# MCU.net
KiCad netlist of a schematic drawn in Altium Designer
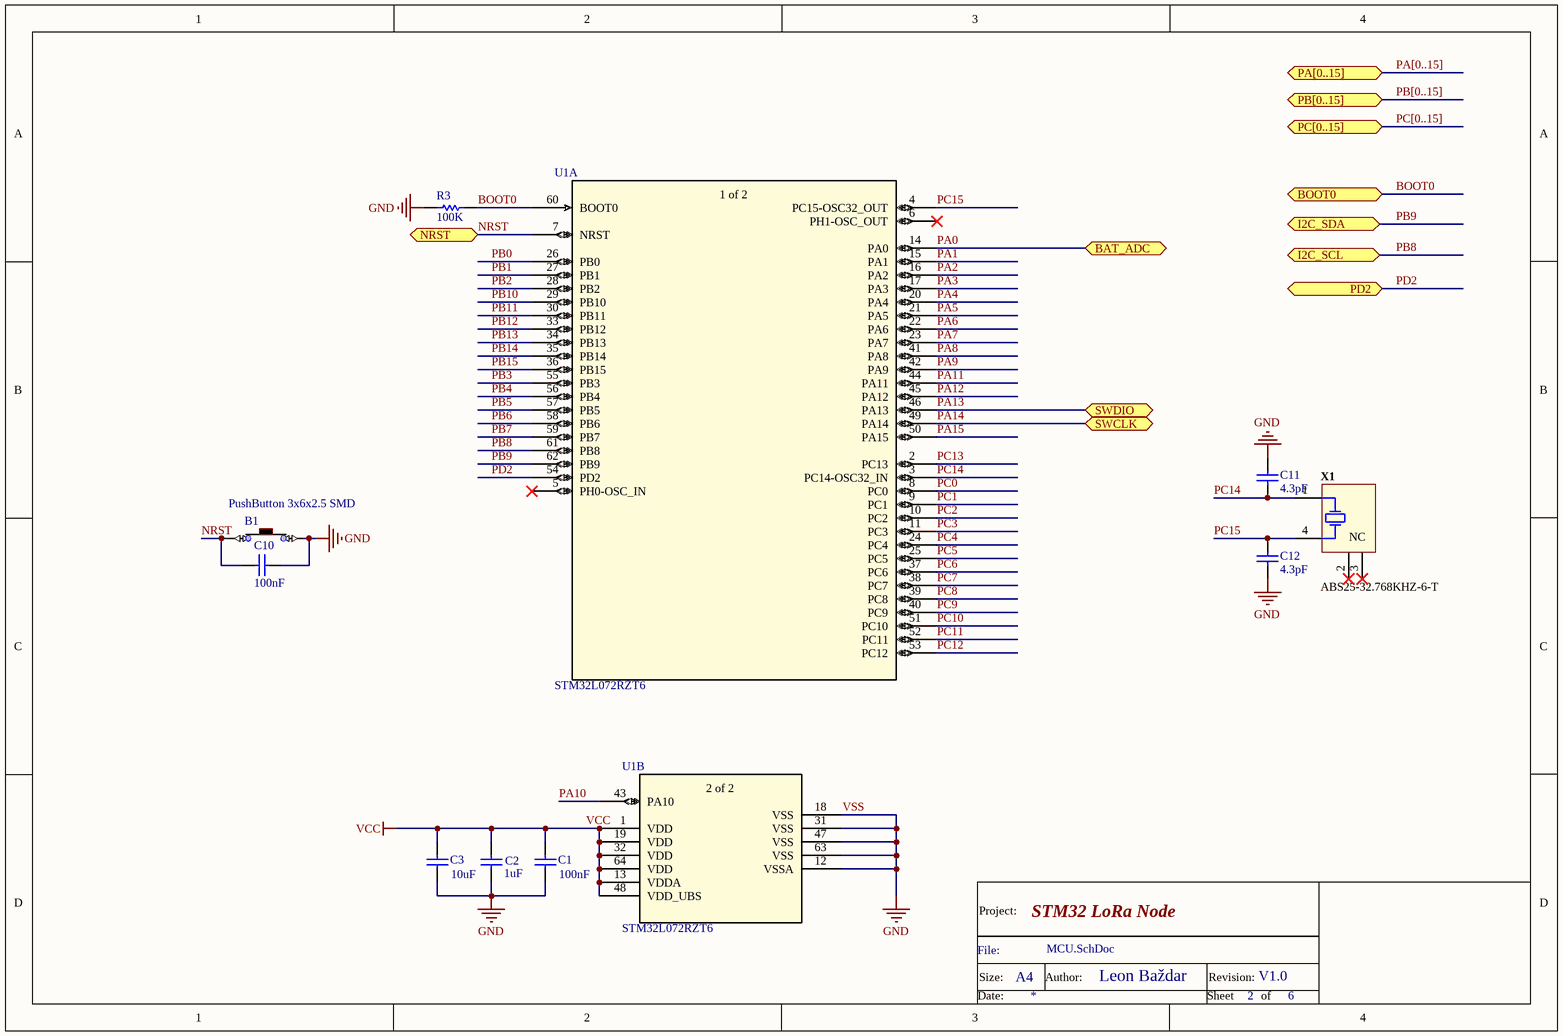
[diagram p0: MCU.SchDoc]

(export (version "E")
  (design (tool "Eeschema 10.0.6"))
  (components
    (comp (ref "B1")
      (value "PushButton 3x6x2.5 SMD")
      (footprint "PushButton 3x6x2.5 SMD-Footprint-1")
      (libsource (lib " Faculty of Electrical Engineering and Computing") (part "PushButton"))
    )
    (comp (ref "C1")
      (value "100nF")
      (footprint "CAPC1005X56X25LL10T15")
      (fields
        (field (name "PART NUMBER") "0402YD104KAT2A")
        (field (name "MANUFACTURER") "AVX Interconnect / Elco")
      )
      (libsource (lib "Altium Content Vault") (part "CAP"))
    )
    (comp (ref "C2")
      (value "1uF")
      (footprint "CAPC2013X145X50LL20T25")
      (fields (field (name "MANUFACTURER") "Kemet") (field (name "PART NUMBER") "C0805C105K4PACTU"))
      (libsource (lib "Altium Content Vault") (part "CAP"))
    )
    (comp (ref "C3")
      (value "10uF")
      (footprint "CAPC2013X145X20ML20")
      (fields
        (field (name "MANUFACTURER") "TDK")
        (field (name "TOLERANCE") "±10%")
        (field (name "PCN PART NUMBER") "MLCCPartNumberChange30/Nov/2012")
      )
      (libsource (lib "Altium Content Vault") (part "CAP-NP-2"))
    )
    (comp (ref "C10")
      (value "100nF")
      (footprint "CAPC1608X90X20LL10")
      (description "Chip Capacitor, 0.1 uF, +/- 10%, 50 V, -55 to 125 degC, 0603 (1608 Metric), RoHS, Tape and Reel")
      (fields (field (name "VOLTAGE") "50V") (field (name "TOLERANCE") "10%"))
      (libsource (lib "Altium Content Vault") (part "CAP-NP-2"))
    )
    (comp (ref "C11")
      (value "4.3pF")
      (footprint "CAPC1608X90X35LL10T15")
      (fields (field (name "PART NUMBER") "GQM1885C2A4R3BB01D") (field (name "MANUFACTURER") "Murata"))
      (libsource (lib "Altium Content Vault") (part "CAP"))
    )
    (comp (ref "C12")
      (value "4.3pF")
      (footprint "CAPC1608X90X35LL10T15")
      (fields (field (name "PART NUMBER") "GQM1885C2A4R3BB01D") (field (name "MANUFACTURER") "Murata"))
      (libsource (lib "Altium Content Vault") (part "CAP"))
    )
    (comp (ref "R3")
      (value "100K")
      (footprint "RESC1005X40X25ML05T05")
      (description "Chip Resistor, 100 KOhm, +/- 1%, 0.63 W, -55 to 155 degC, 0402 (1005 Metric), RoHS, Tape and Reel")
      (fields (field (name "TOLERANCE") "1%"))
      (libsource (lib "Altium Content Vault") (part "RES-2"))
    )
    (comp (ref "U1")
      (value "STM32L072RZT6")
      (footprint "LQFP64-10x10mm")
      (description "No Description Available")
      (fields (field (name "COPYRIGHT") "Copyright (C) 2018 Accelerated Designs. All rights reserved"))
      (libsource (lib "STM32L072RZT6") (part "STM32L072RZT6"))
    )
    (comp (ref "X1")
      (value "ABS25-32.768KHZ-6-T")
      (footprint "ABRA-ABS25-4_V")
      (fields (field (name "TOLERANCE") "20PPM") (field (name "MANUFACTURER") "Abracon"))
      (libsource (lib "Altium Content Vault") (part "ABRA-XTAL_1-4-4"))
    )
  )
  (nets
    (net (code "1") (name "/BOOT0") (class "Default")
      (node (ref "R3") (pin "2") (pinfunction "2_2") (pintype "passive"))
      (node (ref "U1") (pin "60") (pinfunction "BOOT0_60") (pintype "input"))
    )
    (net (code "2") (name "/NRST") (class "Default")
      (node (ref "B1") (pin "1") (pinfunction "b1_1") (pintype "bidirectional"))
      (node (ref "C10") (pin "1") (pinfunction "1_1") (pintype "passive"))
      (node (ref "U1") (pin "7") (pinfunction "NRST_7") (pintype "bidirectional"))
    )
    (net (code "3") (name "/PA0") (class "Default")
      (node (ref "U1") (pin "14") (pinfunction "PA0_14") (pintype "bidirectional"))
    )
    (net (code "4") (name "/PA1") (class "Default")
      (node (ref "U1") (pin "15") (pinfunction "PA1_15") (pintype "bidirectional"))
    )
    (net (code "5") (name "/PA2") (class "Default")
      (node (ref "U1") (pin "16") (pinfunction "PA2_16") (pintype "bidirectional"))
    )
    (net (code "6") (name "/PA3") (class "Default")
      (node (ref "U1") (pin "17") (pinfunction "PA3_17") (pintype "bidirectional"))
    )
    (net (code "7") (name "/PA4") (class "Default")
      (node (ref "U1") (pin "20") (pinfunction "PA4_20") (pintype "bidirectional"))
    )
    (net (code "8") (name "/PA5") (class "Default")
      (node (ref "U1") (pin "21") (pinfunction "PA5_21") (pintype "bidirectional"))
    )
    (net (code "9") (name "/PA6") (class "Default")
      (node (ref "U1") (pin "22") (pinfunction "PA6_22") (pintype "bidirectional"))
    )
    (net (code "10") (name "/PA7") (class "Default")
      (node (ref "U1") (pin "23") (pinfunction "PA7_23") (pintype "bidirectional"))
    )
    (net (code "11") (name "/PA8") (class "Default")
      (node (ref "U1") (pin "41") (pinfunction "PA8_41") (pintype "bidirectional"))
    )
    (net (code "12") (name "/PA9") (class "Default")
      (node (ref "U1") (pin "42") (pinfunction "PA9_42") (pintype "bidirectional"))
    )
    (net (code "13") (name "/PA10") (class "Default")
      (node (ref "U1") (pin "43") (pinfunction "PA10_43") (pintype "bidirectional"))
    )
    (net (code "14") (name "/PA11") (class "Default")
      (node (ref "U1") (pin "44") (pinfunction "PA11_44") (pintype "bidirectional"))
    )
    (net (code "15") (name "/PA12") (class "Default")
      (node (ref "U1") (pin "45") (pinfunction "PA12_45") (pintype "bidirectional"))
    )
    (net (code "16") (name "/PA13") (class "Default")
      (node (ref "U1") (pin "46") (pinfunction "PA13_46") (pintype "bidirectional"))
    )
    (net (code "17") (name "/PA14") (class "Default")
      (node (ref "U1") (pin "49") (pinfunction "PA14_49") (pintype "bidirectional"))
    )
    (net (code "18") (name "/PA15") (class "Default")
      (node (ref "U1") (pin "50") (pinfunction "PA15_50") (pintype "bidirectional"))
    )
    (net (code "20") (name "/PB0") (class "Default")
      (node (ref "U1") (pin "26") (pinfunction "PB0_26") (pintype "bidirectional"))
    )
    (net (code "21") (name "/PB1") (class "Default")
      (node (ref "U1") (pin "27") (pinfunction "PB1_27") (pintype "bidirectional"))
    )
    (net (code "22") (name "/PB2") (class "Default")
      (node (ref "U1") (pin "28") (pinfunction "PB2_28") (pintype "bidirectional"))
    )
    (net (code "23") (name "/PB3") (class "Default")
      (node (ref "U1") (pin "55") (pinfunction "PB3_55") (pintype "bidirectional"))
    )
    (net (code "24") (name "/PB4") (class "Default")
      (node (ref "U1") (pin "56") (pinfunction "PB4_56") (pintype "bidirectional"))
    )
    (net (code "25") (name "/PB5") (class "Default")
      (node (ref "U1") (pin "57") (pinfunction "PB5_57") (pintype "bidirectional"))
    )
    (net (code "26") (name "/PB6") (class "Default")
      (node (ref "U1") (pin "58") (pinfunction "PB6_58") (pintype "bidirectional"))
    )
    (net (code "27") (name "/PB7") (class "Default")
      (node (ref "U1") (pin "59") (pinfunction "PB7_59") (pintype "bidirectional"))
    )
    (net (code "28") (name "/PB8") (class "Default")
      (node (ref "U1") (pin "61") (pinfunction "PB8_61") (pintype "bidirectional"))
    )
    (net (code "29") (name "/PB9") (class "Default")
      (node (ref "U1") (pin "62") (pinfunction "PB9_62") (pintype "bidirectional"))
    )
    (net (code "30") (name "/PB10") (class "Default")
      (node (ref "U1") (pin "29") (pinfunction "PB10_29") (pintype "bidirectional"))
    )
    (net (code "31") (name "/PB11") (class "Default")
      (node (ref "U1") (pin "30") (pinfunction "PB11_30") (pintype "bidirectional"))
    )
    (net (code "32") (name "/PB12") (class "Default")
      (node (ref "U1") (pin "33") (pinfunction "PB12_33") (pintype "bidirectional"))
    )
    (net (code "33") (name "/PB13") (class "Default")
      (node (ref "U1") (pin "34") (pinfunction "PB13_34") (pintype "bidirectional"))
    )
    (net (code "34") (name "/PB14") (class "Default")
      (node (ref "U1") (pin "35") (pinfunction "PB14_35") (pintype "bidirectional"))
    )
    (net (code "35") (name "/PB15") (class "Default")
      (node (ref "U1") (pin "36") (pinfunction "PB15_36") (pintype "bidirectional"))
    )
    (net (code "37") (name "/PC0") (class "Default")
      (node (ref "U1") (pin "8") (pinfunction "PC0_8") (pintype "bidirectional"))
    )
    (net (code "38") (name "/PC1") (class "Default")
      (node (ref "U1") (pin "9") (pinfunction "PC1_9") (pintype "bidirectional"))
    )
    (net (code "39") (name "/PC2") (class "Default")
      (node (ref "U1") (pin "10") (pinfunction "PC2_10") (pintype "bidirectional"))
    )
    (net (code "40") (name "/PC3") (class "Default")
      (node (ref "U1") (pin "11") (pinfunction "PC3_11") (pintype "bidirectional"))
    )
    (net (code "41") (name "/PC4") (class "Default")
      (node (ref "U1") (pin "24") (pinfunction "PC4_24") (pintype "bidirectional"))
    )
    (net (code "42") (name "/PC5") (class "Default")
      (node (ref "U1") (pin "25") (pinfunction "PC5_25") (pintype "bidirectional"))
    )
    (net (code "43") (name "/PC6") (class "Default")
      (node (ref "U1") (pin "37") (pinfunction "PC6_37") (pintype "bidirectional"))
    )
    (net (code "44") (name "/PC7") (class "Default")
      (node (ref "U1") (pin "38") (pinfunction "PC7_38") (pintype "bidirectional"))
    )
    (net (code "45") (name "/PC8") (class "Default")
      (node (ref "U1") (pin "39") (pinfunction "PC8_39") (pintype "bidirectional"))
    )
    (net (code "46") (name "/PC9") (class "Default")
      (node (ref "U1") (pin "40") (pinfunction "PC9_40") (pintype "bidirectional"))
    )
    (net (code "47") (name "/PC10") (class "Default")
      (node (ref "U1") (pin "51") (pinfunction "PC10_51") (pintype "bidirectional"))
    )
    (net (code "48") (name "/PC11") (class "Default")
      (node (ref "U1") (pin "52") (pinfunction "PC11_52") (pintype "bidirectional"))
    )
    (net (code "49") (name "/PC12") (class "Default")
      (node (ref "U1") (pin "53") (pinfunction "PC12_53") (pintype "bidirectional"))
    )
    (net (code "50") (name "/PC13") (class "Default")
      (node (ref "U1") (pin "2") (pinfunction "PC13_2") (pintype "bidirectional"))
    )
    (net (code "51") (name "/PC14") (class "Default")
      (node (ref "C11") (pin "1") (pinfunction "1_1") (pintype "passive"))
      (node (ref "U1") (pin "3") (pinfunction "PC14-OSC32_IN_3") (pintype "bidirectional"))
      (node (ref "X1") (pin "1") (pinfunction "X1_1") (pintype "passive"))
    )
    (net (code "52") (name "/PC15") (class "Default")
      (node (ref "C12") (pin "2") (pinfunction "2_2") (pintype "passive"))
      (node (ref "U1") (pin "4") (pinfunction "PC15-OSC32_OUT_4") (pintype "bidirectional"))
      (node (ref "X1") (pin "4") (pinfunction "X2_4") (pintype "passive"))
    )
    (net (code "54") (name "/PD2") (class "Default")
      (node (ref "U1") (pin "54") (pinfunction "PD2_54") (pintype "bidirectional"))
    )
    (net (code "55") (name "GND") (class "Default")
      (node (ref "B1") (pin "2") (pinfunction "b2_2") (pintype "bidirectional"))
      (node (ref "C1") (pin "2") (pinfunction "2_2") (pintype "passive"))
      (node (ref "C10") (pin "2") (pinfunction "2_2") (pintype "passive"))
      (node (ref "C11") (pin "2") (pinfunction "2_2") (pintype "passive"))
      (node (ref "C12") (pin "1") (pinfunction "1_1") (pintype "passive"))
      (node (ref "C2") (pin "2") (pinfunction "2_2") (pintype "passive"))
      (node (ref "C3") (pin "1") (pinfunction "1_1") (pintype "passive"))
      (node (ref "R3") (pin "1") (pinfunction "1_1") (pintype "passive"))
      (node (ref "U1") (pin "12") (pinfunction "VSSA_12") (pintype "power_in"))
      (node (ref "U1") (pin "18") (pinfunction "VSS_18") (pintype "power_in"))
      (node (ref "U1") (pin "31") (pinfunction "VSS_31") (pintype "power_in"))
      (node (ref "U1") (pin "47") (pinfunction "VSS_47") (pintype "power_in"))
      (node (ref "U1") (pin "63") (pinfunction "VSS_63") (pintype "power_in"))
    )
    (net (code "56") (name "VCC") (class "Default")
      (node (ref "C1") (pin "1") (pinfunction "1_1") (pintype "passive"))
      (node (ref "C2") (pin "1") (pinfunction "1_1") (pintype "passive"))
      (node (ref "C3") (pin "2") (pinfunction "2_2") (pintype "passive"))
      (node (ref "U1") (pin "1") (pinfunction "VDD_1") (pintype "power_in"))
      (node (ref "U1") (pin "13") (pinfunction "VDDA_13") (pintype "power_in"))
      (node (ref "U1") (pin "19") (pinfunction "VDD_19") (pintype "power_in"))
      (node (ref "U1") (pin "32") (pinfunction "VDD_32") (pintype "power_in"))
      (node (ref "U1") (pin "48") (pinfunction "VDD_UBS_48") (pintype "power_in"))
      (node (ref "U1") (pin "64") (pinfunction "VDD_64") (pintype "power_in"))
    )
    (net (code "57") (name "unconnected-(U1A-PH0-OSC_IN-Pad5)") (class "Default")
      (node (ref "U1") (pin "5") (pinfunction "PH0-OSC_IN_5") (pintype "bidirectional+no_connect"))
    )
    (net (code "58") (name "unconnected-(U1A-PH1-OSC_OUT-Pad6)") (class "Default")
      (node (ref "U1") (pin "6") (pinfunction "PH1-OSC_OUT_6") (pintype "bidirectional+no_connect"))
    )
    (net (code "59") (name "unconnected-(X1-NC-Pad2)") (class "Default")
      (node (ref "X1") (pin "2") (pinfunction "NC_2") (pintype "passive+no_connect"))
    )
    (net (code "60") (name "unconnected-(X1-NC-Pad3)") (class "Default")
      (node (ref "X1") (pin "3") (pinfunction "NC_3") (pintype "passive+no_connect"))
    )
  )
)
